# Schematic.net
KiCad netlist of a schematic drawn in EAGLE
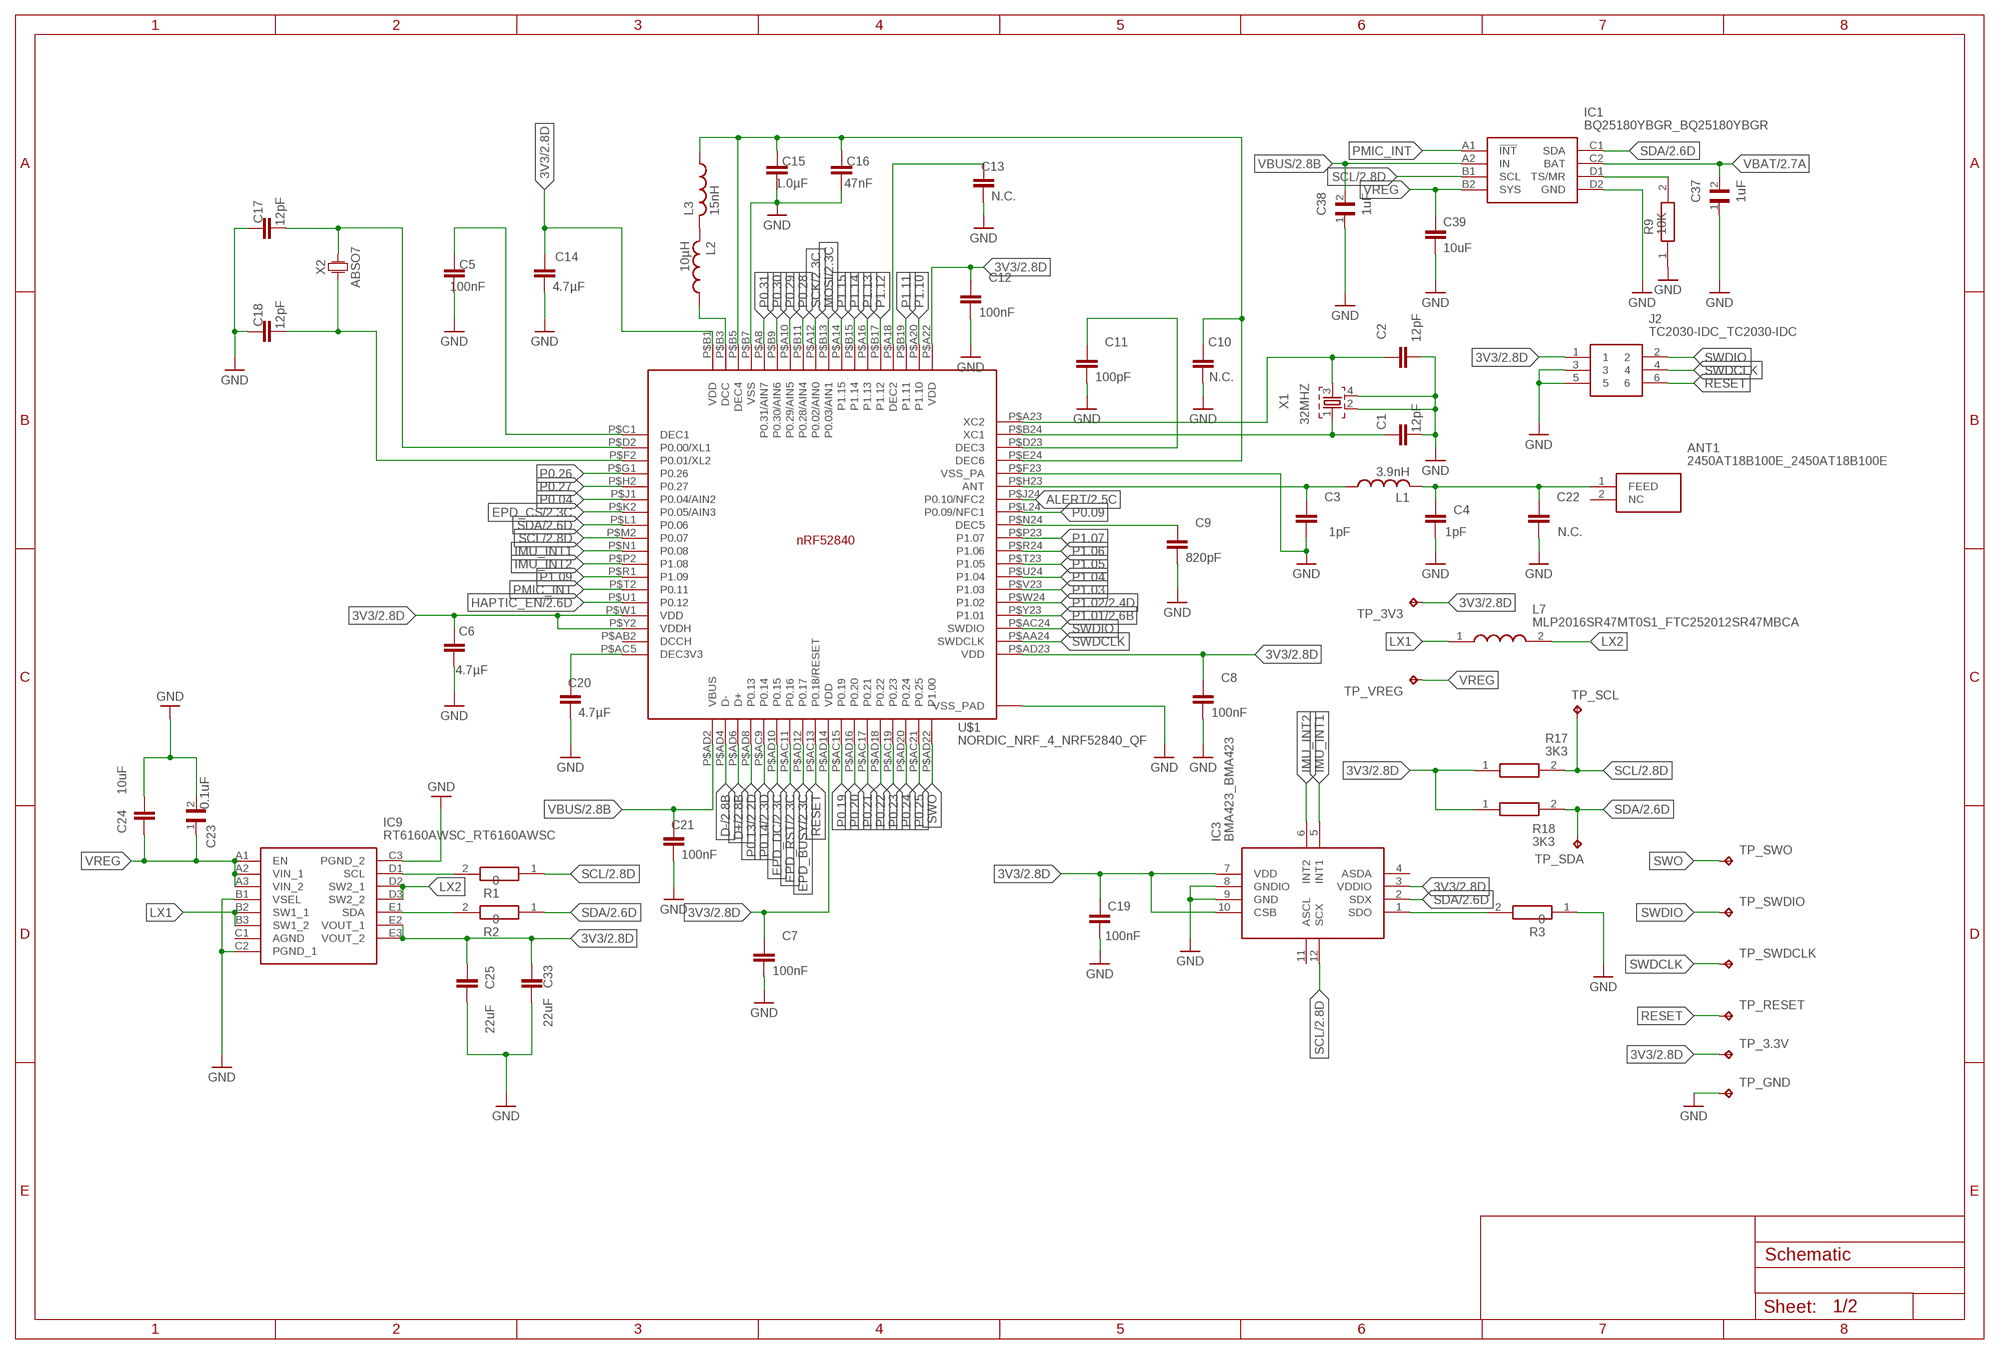
[diagram p0: schematic, sheet 1]
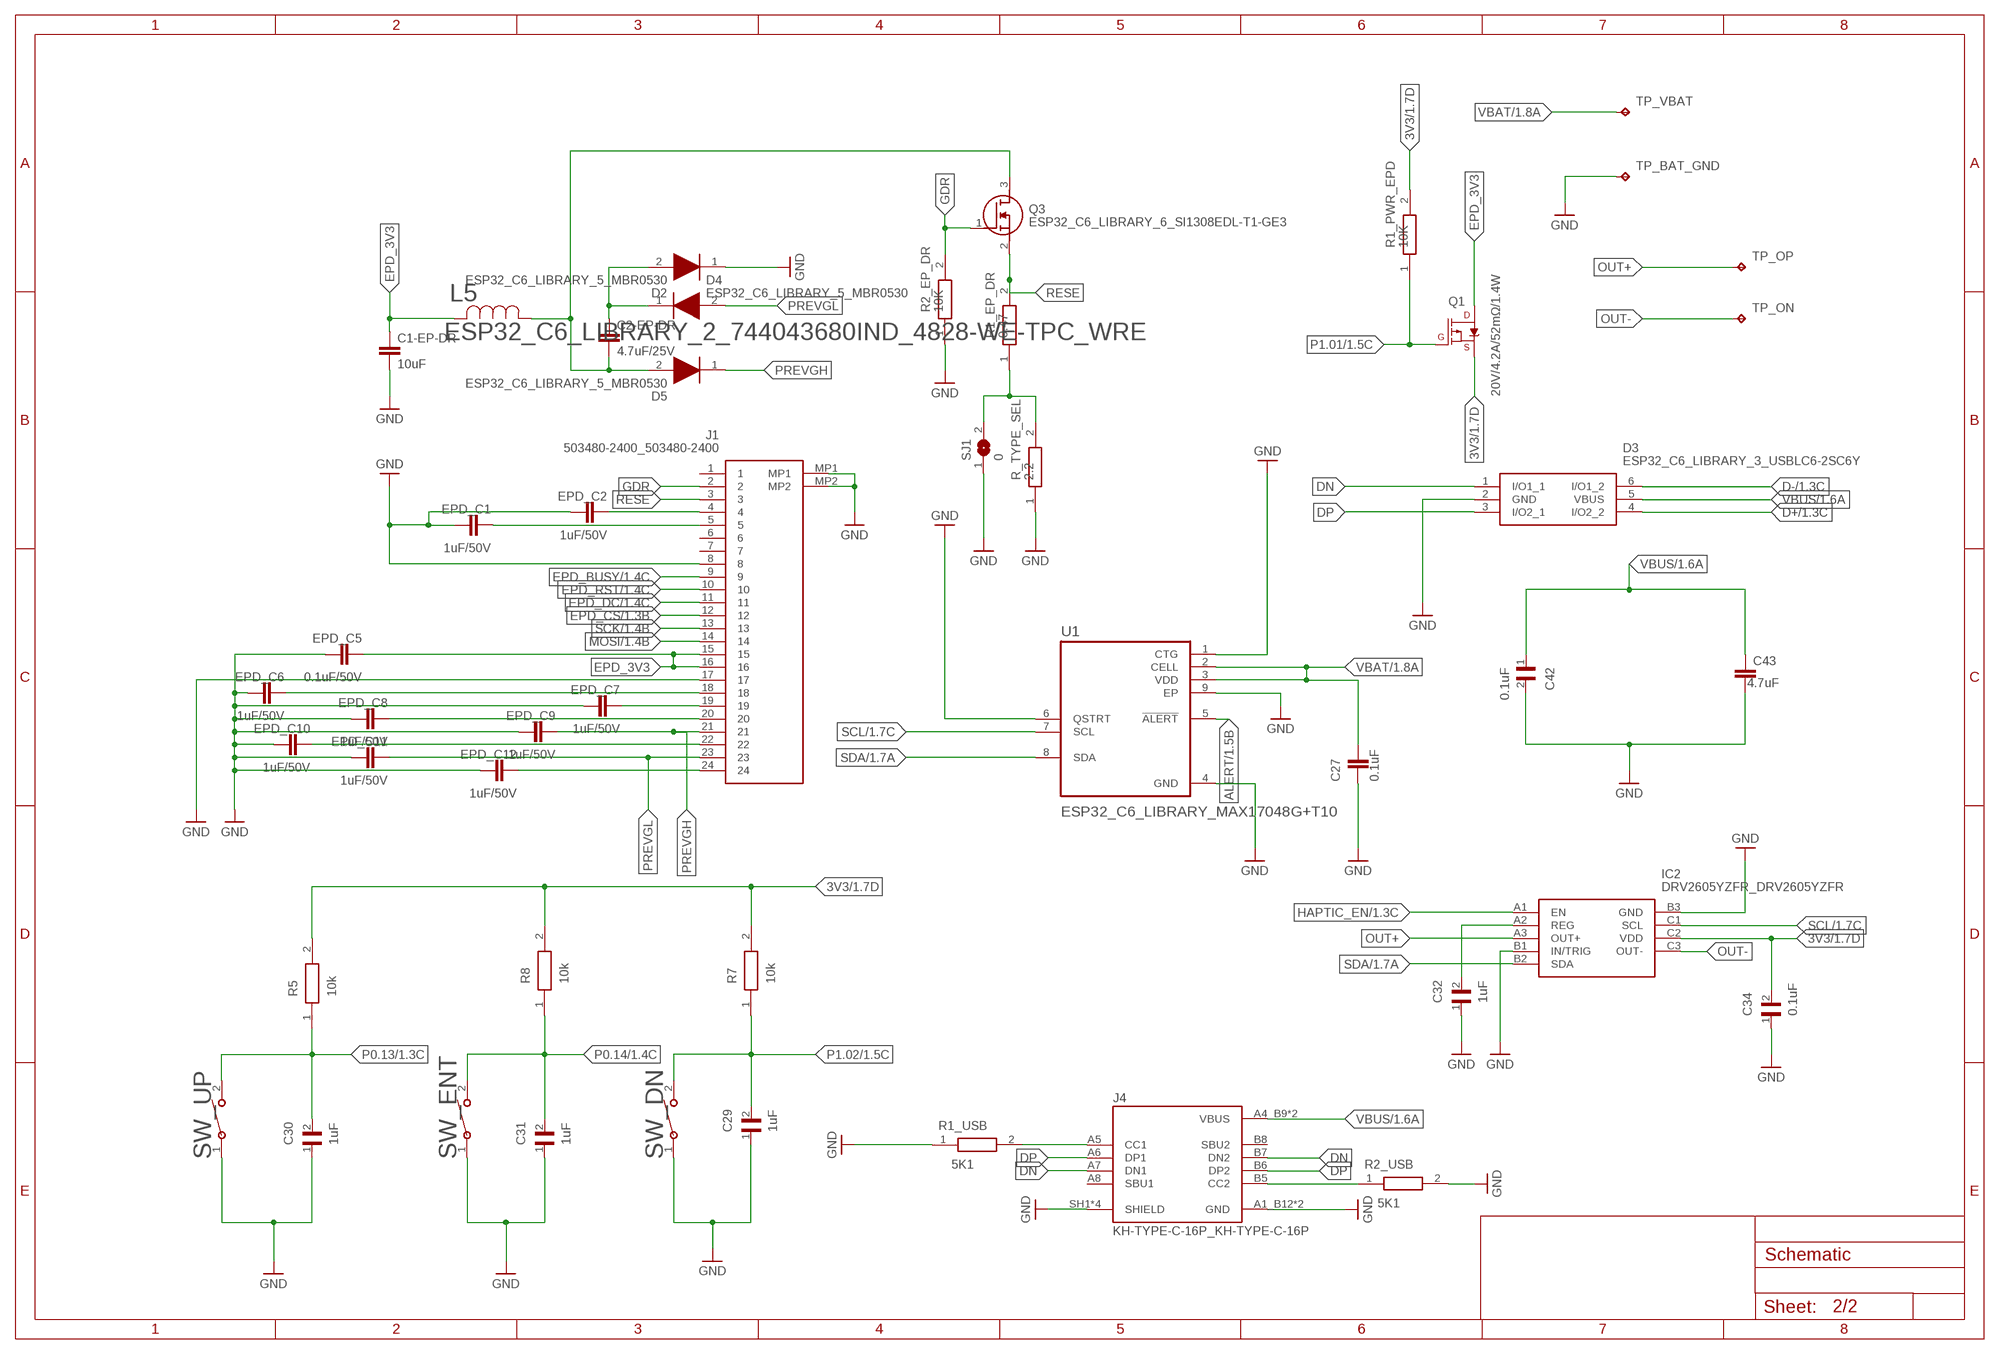
[diagram p1: schematic, sheet 2]

(export (version "E")
  (design (tool "Eeschema 10.0.6"))
  (components
    (comp (ref "C1-EP-DR")
      (value "10uF")
      (footprint "eagle-import:NORDIC_NRF_3_RESC0201_L")
      (libsource (lib "eagle-import") (part "InkTime_v5_vf.HE5F4i0kSp2JyauVwp79Dg_NORDIC_NRF_3_CAPACITOR_0201_L"))
    )
    (comp (ref "C2-EP-DR")
      (value "4.7uF/25V")
      (footprint "eagle-import:NORDIC_NRF_3_RESC0201_L")
      (libsource (lib "eagle-import") (part "InkTime_v5_vf.HE5F4i0kSp2JyauVwp79Dg_NORDIC_NRF_3_CAPACITOR_0201_L"))
    )
    (comp (ref "C27")
      (value "0.1uF")
      (footprint "eagle-import:NORDIC_NRF_3_RESC0201_L")
      (libsource (lib "eagle-import") (part "InkTime_v5_vf.HE5F4i0kSp2JyauVwp79Dg_NORDIC_NRF_3_CAPACITOR_0201_L"))
    )
    (comp (ref "C29")
      (value "1uF")
      (footprint "eagle-import:GRM011R60J152KE01L_1_0201")
      (libsource (lib "eagle-import") (part "GRM011R60J152KE01L_1_GRM011R60J152KE01L"))
    )
    (comp (ref "C30")
      (value "1uF")
      (footprint "eagle-import:GRM011R60J152KE01L_1_0201")
      (libsource (lib "eagle-import") (part "GRM011R60J152KE01L_1_GRM011R60J152KE01L"))
    )
    (comp (ref "C31")
      (value "1uF")
      (footprint "eagle-import:GRM011R60J152KE01L_1_0201")
      (libsource (lib "eagle-import") (part "GRM011R60J152KE01L_1_GRM011R60J152KE01L"))
    )
    (comp (ref "C32")
      (value "1uF")
      (footprint "eagle-import:GRM011R60J152KE01L_1_0201")
      (libsource (lib "eagle-import") (part "GRM011R60J152KE01L_1_GRM011R60J152KE01L"))
    )
    (comp (ref "C34")
      (value "0.1uF")
      (footprint "eagle-import:GRM011R60J152KE01L_1_0201")
      (libsource (lib "eagle-import") (part "GRM011R60J152KE01L_1_GRM011R60J152KE01L"))
    )
    (comp (ref "C42")
      (value "0.1uF")
      (footprint "eagle-import:GRM011R60J152KE01L_1_0201")
      (libsource (lib "eagle-import") (part "GRM011R60J152KE01L_1_GRM011R60J152KE01L"))
    )
    (comp (ref "C43")
      (value "4.7uF")
      (footprint "eagle-import:NORDIC_NRF_3_RESC0201_L")
      (libsource (lib "eagle-import") (part "InkTime_v5_vf.HE5F4i0kSp2JyauVwp79Dg_NORDIC_NRF_3_CAPACITOR_0201_L"))
    )
    (comp (ref "D2")
      (value "ESP32_C6_LIBRARY_5_MBR0530")
      (footprint "eagle-import:ESP32_C6_LIBRARY_5_SOD3716X135N")
      (fields (field (name "MF") "ON Semiconductor") (field (name "MP") "MBR0530"))
      (libsource (lib "eagle-import") (part "ESP32_C6_LIBRARY_5_MBR0530"))
    )
    (comp (ref "D3")
      (value "ESP32_C6_LIBRARY_3_USBLC6-2SC6Y")
      (footprint "eagle-import:ESP32_C6_LIBRARY_3_SOT95P280X145-6N")
      (fields (field (name "MF") "STMicroelectronics") (field (name "MP") "USBLC6-2SC6Y"))
      (libsource (lib "eagle-import") (part "ESP32_C6_LIBRARY_3_USBLC6-2SC6Y"))
    )
    (comp (ref "D4")
      (value "ESP32_C6_LIBRARY_5_MBR0530")
      (footprint "eagle-import:ESP32_C6_LIBRARY_5_SOD3716X135N")
      (fields (field (name "MF") "ON Semiconductor") (field (name "MP") "MBR0530"))
      (libsource (lib "eagle-import") (part "ESP32_C6_LIBRARY_5_MBR0530"))
    )
    (comp (ref "D5")
      (value "ESP32_C6_LIBRARY_5_MBR0530")
      (footprint "eagle-import:ESP32_C6_LIBRARY_5_SOD3716X135N")
      (fields (field (name "MF") "ON Semiconductor") (field (name "MP") "MBR0530"))
      (libsource (lib "eagle-import") (part "ESP32_C6_LIBRARY_5_MBR0530"))
    )
    (comp (ref "EPD_C1")
      (value "1uF/50V")
      (footprint "eagle-import:NORDIC_NRF_3_RESC0201_L")
      (libsource (lib "eagle-import") (part "InkTime_v5_vf.HE5F4i0kSp2JyauVwp79Dg_NORDIC_NRF_3_CAPACITOR_0201_L"))
    )
    (comp (ref "EPD_C2")
      (value "1uF/50V")
      (footprint "eagle-import:NORDIC_NRF_3_RESC0201_L")
      (libsource (lib "eagle-import") (part "InkTime_v5_vf.HE5F4i0kSp2JyauVwp79Dg_NORDIC_NRF_3_CAPACITOR_0201_L"))
    )
    (comp (ref "EPD_C5")
      (value "0.1uF/50V")
      (footprint "eagle-import:NORDIC_NRF_3_RESC0201_L")
      (libsource (lib "eagle-import") (part "InkTime_v5_vf.HE5F4i0kSp2JyauVwp79Dg_NORDIC_NRF_3_CAPACITOR_0201_L"))
    )
    (comp (ref "EPD_C6")
      (value "1uF/50V")
      (footprint "eagle-import:NORDIC_NRF_3_RESC0201_L")
      (libsource (lib "eagle-import") (part "InkTime_v5_vf.HE5F4i0kSp2JyauVwp79Dg_NORDIC_NRF_3_CAPACITOR_0201_L"))
    )
    (comp (ref "EPD_C7")
      (value "1uF/50V")
      (footprint "eagle-import:NORDIC_NRF_3_RESC0201_L")
      (libsource (lib "eagle-import") (part "InkTime_v5_vf.HE5F4i0kSp2JyauVwp79Dg_NORDIC_NRF_3_CAPACITOR_0201_L"))
    )
    (comp (ref "EPD_C8")
      (value "1uF/50V")
      (footprint "eagle-import:NORDIC_NRF_3_RESC0201_L")
      (libsource (lib "eagle-import") (part "InkTime_v5_vf.HE5F4i0kSp2JyauVwp79Dg_NORDIC_NRF_3_CAPACITOR_0201_L"))
    )
    (comp (ref "EPD_C9")
      (value "1uF/50V")
      (footprint "eagle-import:NORDIC_NRF_3_RESC0201_L")
      (libsource (lib "eagle-import") (part "InkTime_v5_vf.HE5F4i0kSp2JyauVwp79Dg_NORDIC_NRF_3_CAPACITOR_0201_L"))
    )
    (comp (ref "EPD_C10")
      (value "1uF/50V")
      (footprint "eagle-import:NORDIC_NRF_3_RESC0201_L")
      (libsource (lib "eagle-import") (part "InkTime_v5_vf.HE5F4i0kSp2JyauVwp79Dg_NORDIC_NRF_3_CAPACITOR_0201_L"))
    )
    (comp (ref "EPD_C11")
      (value "1uF/50V")
      (footprint "eagle-import:NORDIC_NRF_3_RESC0201_L")
      (libsource (lib "eagle-import") (part "InkTime_v5_vf.HE5F4i0kSp2JyauVwp79Dg_NORDIC_NRF_3_CAPACITOR_0201_L"))
    )
    (comp (ref "EPD_C12")
      (value "1uF/50V")
      (footprint "eagle-import:NORDIC_NRF_3_RESC0201_L")
      (libsource (lib "eagle-import") (part "InkTime_v5_vf.HE5F4i0kSp2JyauVwp79Dg_NORDIC_NRF_3_CAPACITOR_0201_L"))
    )
    (comp (ref "IC2")
      (value "DRV2605YZFR_DRV2605YZFR")
      (footprint "eagle-import:DRV2605YZFR_BGA9C50P3X3_144X144X62")
      (fields (field (name "MANUFACTURER_PART_NUMBER") "DRV2605YZFR"))
      (libsource (lib "eagle-import") (part "DRV2605YZFR_DRV2605YZFR"))
    )
    (comp (ref "J1")
      (value "503480-2400_503480-2400")
      (footprint "eagle-import:503480-2400_5034802400")
      (fields
        (field (name "MANUFACTURER_PART_NUMBER") "503480-2400")
        (field (name "MOUSER_PART_NUMBER") "538-503480-2400")
      )
      (libsource (lib "eagle-import") (part "503480-2400_503480-2400"))
    )
    (comp (ref "J4")
      (value "KH-TYPE-C-16P_KH-TYPE-C-16P")
      (footprint "eagle-import:KH-TYPE-C-16P_KINGHELM_KH-TYPE-C-16P")
      (fields (field (name "MF") "kinghelm") (field (name "MP") "KH-TYPE-C-16P"))
      (libsource (lib "eagle-import") (part "KH-TYPE-C-16P_KH-TYPE-C-16P"))
    )
    (comp (ref "L5")
      (value "ESP32_C6_LIBRARY_2_744043680IND_4828-WE-TPC_WRE")
      (footprint "eagle-import:ESP32_C6_LIBRARY_2_IND_4828-WE-TPC_WRE")
      (fields
        (field (name "MANUFACTURER_PART_NUMBER") "744043680")
        (field (name "COPYRIGHT") "Copyright (C) 2024 Ultra Librarian. All rights reserved.")
      )
      (libsource (lib "eagle-import") (part "ESP32_C6_LIBRARY_2_744043680IND_4828-WE-TPC_WRE"))
    )
    (comp (ref "Q1")
      (value "20V/4.2A/52mΩ/1.4W")
      (footprint "eagle-import:ESP32_C6_LIBRARY_4_ESP32_C6_LIBRARY_4_ESP32_C6_LIBRARY_4_ESP32_C6_LIBRARY_4_ESP32_WROVER_SPARKFUN-DISCRETESEMI_SOT23-3")
      (libsource (lib "eagle-import") (part "ESP32_C6_LIBRARY_4_ESP32_WROVER_SPARKFUN-DISCRETESEMI_MOSFET_PCH-DMG2305UX-7"))
    )
    (comp (ref "Q3")
      (value "ESP32_C6_LIBRARY_6_SI1308EDL-T1-GE3")
      (footprint "eagle-import:ESP32_C6_LIBRARY_6_SOT65P210X110-3N")
      (fields (field (name "MF") "Vishay Siliconix") (field (name "MP") "SI1308EDL-T1-GE3"))
      (libsource (lib "eagle-import") (part "ESP32_C6_LIBRARY_6_SI1308EDL-T1-GE3"))
    )
    (comp (ref "R1_EP_DR")
      (value "0.47")
      (footprint "eagle-import:CPF0201D7K68C1_0201")
      (libsource (lib "eagle-import") (part "InkTime_v5_vf.HE5F4i0kSp2JyauVwp79Dg_CPF0201D7K68C1_CPF0201D7K68C1"))
    )
    (comp (ref "R1_PWR_EPD")
      (value "10K")
      (footprint "eagle-import:CPF0201D7K68C1_0201")
      (libsource (lib "eagle-import") (part "InkTime_v5_vf.HE5F4i0kSp2JyauVwp79Dg_CPF0201D7K68C1_CPF0201D7K68C1"))
    )
    (comp (ref "R1_USB")
      (value "5K1")
      (footprint "eagle-import:CPF0201D7K68C1_0201")
      (libsource (lib "eagle-import") (part "CPF0201D7K68C1_CPF0201D7K68C1"))
    )
    (comp (ref "R2_EP_DR")
      (value "10K")
      (footprint "eagle-import:CPF0201D7K68C1_0201")
      (libsource (lib "eagle-import") (part "InkTime_v5_vf.HE5F4i0kSp2JyauVwp79Dg_CPF0201D7K68C1_CPF0201D7K68C1"))
    )
    (comp (ref "R2_USB")
      (value "5K1")
      (footprint "eagle-import:CPF0201D7K68C1_0201")
      (libsource (lib "eagle-import") (part "CPF0201D7K68C1_CPF0201D7K68C1"))
    )
    (comp (ref "R5")
      (value "10k")
      (footprint "eagle-import:CPF0201D7K68C1_0201")
      (libsource (lib "eagle-import") (part "CPF0201D7K68C1_CPF0201D7K68C1"))
    )
    (comp (ref "R7")
      (value "10k")
      (footprint "eagle-import:CPF0201D7K68C1_0201")
      (libsource (lib "eagle-import") (part "CPF0201D7K68C1_CPF0201D7K68C1"))
    )
    (comp (ref "R8")
      (value "10k")
      (footprint "eagle-import:CPF0201D7K68C1_0201")
      (libsource (lib "eagle-import") (part "CPF0201D7K68C1_CPF0201D7K68C1"))
    )
    (comp (ref "R_TYPE_SEL")
      (value "2.2")
      (footprint "eagle-import:CPF0201D7K68C1_0201")
      (libsource (lib "eagle-import") (part "InkTime_v5_vf.HE5F4i0kSp2JyauVwp79Dg_CPF0201D7K68C1_CPF0201D7K68C1"))
    )
    (comp (ref "SJ1")
      (value "0")
      (footprint "eagle-import:ESP32_C6_LIBRARY_7_JUMPER_SJ")
      (libsource (lib "eagle-import") (part "ESP32_C6_LIBRARY_7_JUMPER_SJ"))
    )
    (comp (ref "SW_DN")
      (value "2025-10-22_07-23-44_LIBRARY_EVP-AKE31ASW_EVP-AKE31A_PAN")
      (footprint "eagle-import:2025-10-22_07-23-44_LIBRARY_SW_EVP-AKE31A_PAN")
      (fields
        (field (name "MANUFACTURER_PART_NUMBER") "EVP-AKE31A")
        (field (name "COPYRIGHT") "Copyright (C) 2025 Ultra Librarian. All rights reserved.")
      )
      (libsource (lib "eagle-import") (part "2025-10-22_07-23-44_LIBRARY_EVP-AKE31ASW_EVP-AKE31A_PAN"))
    )
    (comp (ref "SW_ENT")
      (value "2025-10-22_07-23-44_LIBRARY_EVP-AKE31ASW_EVP-AKE31A_PAN")
      (footprint "eagle-import:2025-10-22_07-23-44_LIBRARY_SW_EVP-AKE31A_PAN")
      (fields
        (field (name "MANUFACTURER_PART_NUMBER") "EVP-AKE31A")
        (field (name "COPYRIGHT") "Copyright (C) 2025 Ultra Librarian. All rights reserved.")
      )
      (libsource (lib "eagle-import") (part "2025-10-22_07-23-44_LIBRARY_EVP-AKE31ASW_EVP-AKE31A_PAN"))
    )
    (comp (ref "SW_UP")
      (value "2025-10-22_07-23-44_LIBRARY_EVP-AKE31ASW_EVP-AKE31A_PAN")
      (footprint "eagle-import:2025-10-22_07-23-44_LIBRARY_SW_EVP-AKE31A_PAN")
      (fields
        (field (name "MANUFACTURER_PART_NUMBER") "EVP-AKE31A")
        (field (name "COPYRIGHT") "Copyright (C) 2025 Ultra Librarian. All rights reserved.")
      )
      (libsource (lib "eagle-import") (part "2025-10-22_07-23-44_LIBRARY_EVP-AKE31ASW_EVP-AKE31A_PAN"))
    )
    (comp (ref "TP_BAT_GND")
      (value "HECTOR_WATCH_1_TPTP20R")
      (footprint "eagle-import:HECTOR_WATCH_1_TP20R")
      (libsource (lib "eagle-import") (part "HECTOR_WATCH_1_TPTP20R"))
    )
    (comp (ref "TP_ON")
      (value "HECTOR_WATCH_1_TPTP20R")
      (footprint "eagle-import:HECTOR_WATCH_1_TP20R")
      (libsource (lib "eagle-import") (part "HECTOR_WATCH_1_TPTP20R"))
    )
    (comp (ref "TP_OP")
      (value "HECTOR_WATCH_1_TPTP20R")
      (footprint "eagle-import:HECTOR_WATCH_1_TP20R")
      (libsource (lib "eagle-import") (part "HECTOR_WATCH_1_TPTP20R"))
    )
    (comp (ref "TP_VBAT")
      (value "HECTOR_WATCH_1_TPTP20R")
      (footprint "eagle-import:HECTOR_WATCH_1_TP20R")
      (libsource (lib "eagle-import") (part "HECTOR_WATCH_1_TPTP20R"))
    )
    (comp (ref "U1")
      (value "ESP32_C6_LIBRARY_MAX17048G+T10")
      (footprint "eagle-import:ESP32_C6_LIBRARY_SON50P200X200X80-9N")
      (fields (field (name "MF") "Analog Devices") (field (name "MP") "MAX17048G+T10"))
      (libsource (lib "eagle-import") (part "ESP32_C6_LIBRARY_MAX17048G+T10"))
    )
    (comp (ref "ANT1")
      (value "2450AT18B100E_2450AT18B100E")
      (footprint "eagle-import:2450AT18B100E_ANTC3216X140N")
      (fields
        (field (name "ARROW_PART_NUMBER") "2450AT18B100E")
        (field (name "MOUSER_PART_NUMBER") "609-2450AT18B100E")
      )
      (libsource (lib "eagle-import") (part "2450AT18B100E_2450AT18B100E"))
    )
    (comp (ref "C1")
      (value "12pF")
      (footprint "eagle-import:NORDIC_NRF_3_RESC0201_L")
      (libsource (lib "eagle-import") (part "NORDIC_NRF_3_CAPACITOR_0201_L"))
    )
    (comp (ref "C2")
      (value "12pF")
      (footprint "eagle-import:NORDIC_NRF_3_RESC0201_L")
      (libsource (lib "eagle-import") (part "NORDIC_NRF_3_CAPACITOR_0201_L"))
    )
    (comp (ref "C3")
      (value "1pF")
      (footprint "eagle-import:NORDIC_NRF_3_RESC0201_L")
      (libsource (lib "eagle-import") (part "NORDIC_NRF_3_CAPACITOR_0201_L"))
    )
    (comp (ref "C4")
      (value "1pF")
      (footprint "eagle-import:NORDIC_NRF_3_RESC0201_L")
      (libsource (lib "eagle-import") (part "NORDIC_NRF_3_CAPACITOR_0201_L"))
    )
    (comp (ref "C5")
      (value "100nF")
      (footprint "eagle-import:NORDIC_NRF_3_RESC0201_L")
      (libsource (lib "eagle-import") (part "NORDIC_NRF_3_CAPACITOR_0201_L"))
    )
    (comp (ref "C6")
      (value "4.7µF")
      (footprint "eagle-import:NORDIC_NRF_3_RESC0201_L")
      (libsource (lib "eagle-import") (part "NORDIC_NRF_3_CAPACITOR_0201_L"))
    )
    (comp (ref "C7")
      (value "100nF")
      (footprint "eagle-import:NORDIC_NRF_3_RESC0201_L")
      (libsource (lib "eagle-import") (part "NORDIC_NRF_3_CAPACITOR_0201_L"))
    )
    (comp (ref "C8")
      (value "100nF")
      (footprint "eagle-import:NORDIC_NRF_3_RESC0201_L")
      (libsource (lib "eagle-import") (part "NORDIC_NRF_3_CAPACITOR_0201_L"))
    )
    (comp (ref "C9")
      (value "820pF")
      (footprint "eagle-import:NORDIC_NRF_3_RESC0201_L")
      (libsource (lib "eagle-import") (part "NORDIC_NRF_3_CAPACITOR_0201_L"))
    )
    (comp (ref "C10")
      (value "N.C.")
      (footprint "eagle-import:NORDIC_NRF_3_RESC0201_L")
      (libsource (lib "eagle-import") (part "NORDIC_NRF_3_CAPACITOR_0201_L"))
    )
    (comp (ref "C11")
      (value "100pF")
      (footprint "eagle-import:NORDIC_NRF_3_RESC0201_L")
      (libsource (lib "eagle-import") (part "NORDIC_NRF_3_CAPACITOR_0201_L"))
    )
    (comp (ref "C12")
      (value "100nF")
      (footprint "eagle-import:NORDIC_NRF_3_RESC0201_L")
      (libsource (lib "eagle-import") (part "NORDIC_NRF_3_CAPACITOR_0201_L"))
    )
    (comp (ref "C13")
      (value "N.C.")
      (footprint "eagle-import:NORDIC_NRF_3_RESC0201_L")
      (libsource (lib "eagle-import") (part "NORDIC_NRF_3_CAPACITOR_0201_L"))
    )
    (comp (ref "C14")
      (value "4.7µF")
      (footprint "eagle-import:NORDIC_NRF_3_RESC0201_L")
      (libsource (lib "eagle-import") (part "NORDIC_NRF_3_CAPACITOR_0201_L"))
    )
    (comp (ref "C15")
      (value "1.0µF")
      (footprint "eagle-import:NORDIC_NRF_3_RESC0201_L")
      (libsource (lib "eagle-import") (part "NORDIC_NRF_3_CAPACITOR_0201_L"))
    )
    (comp (ref "C16")
      (value "47nF")
      (footprint "eagle-import:NORDIC_NRF_3_RESC0201_L")
      (libsource (lib "eagle-import") (part "NORDIC_NRF_3_CAPACITOR_0201_L"))
    )
    (comp (ref "C17")
      (value "12pF")
      (footprint "eagle-import:NORDIC_NRF_3_RESC0201_L")
      (libsource (lib "eagle-import") (part "NORDIC_NRF_3_CAPACITOR_0201_L"))
    )
    (comp (ref "C18")
      (value "12pF")
      (footprint "eagle-import:NORDIC_NRF_3_RESC0201_L")
      (libsource (lib "eagle-import") (part "NORDIC_NRF_3_CAPACITOR_0201_L"))
    )
    (comp (ref "C19")
      (value "100nF")
      (footprint "eagle-import:NORDIC_NRF_3_RESC0201_L")
      (libsource (lib "eagle-import") (part "NORDIC_NRF_3_CAPACITOR_0201_L"))
    )
    (comp (ref "C20")
      (value "4.7µF")
      (footprint "eagle-import:NORDIC_NRF_3_RESC0201_L")
      (libsource (lib "eagle-import") (part "NORDIC_NRF_3_CAPACITOR_0201_L"))
    )
    (comp (ref "C21")
      (value "100nF")
      (footprint "eagle-import:NORDIC_NRF_3_RESC0201_L")
      (libsource (lib "eagle-import") (part "NORDIC_NRF_3_CAPACITOR_0201_L"))
    )
    (comp (ref "C22")
      (value "N.C.")
      (footprint "eagle-import:NORDIC_NRF_3_RESC0201_L")
      (libsource (lib "eagle-import") (part "NORDIC_NRF_3_CAPACITOR_0201_L"))
    )
    (comp (ref "C23")
      (value "0.1uF")
      (footprint "eagle-import:GRM011R60J152KE01L_2_CAPC0201X13N")
      (fields (field (name "MF") "Murata") (field (name "MP") "GRM011R60J152KE01L"))
      (libsource (lib "eagle-import") (part "GRM011R60J152KE01L_2_GRM011R60J152KE01L"))
    )
    (comp (ref "C24")
      (value "10uF")
      (footprint "eagle-import:NORDIC_NRF_3_RESC0201_L")
      (libsource (lib "eagle-import") (part "NORDIC_NRF_3_CAPACITOR_0201_L"))
    )
    (comp (ref "C25")
      (value "22uF")
      (footprint "eagle-import:NORDIC_NRF_3_RESC0201_L")
      (libsource (lib "eagle-import") (part "NORDIC_NRF_3_CAPACITOR_0201_L"))
    )
    (comp (ref "C33")
      (value "22uF")
      (footprint "eagle-import:NORDIC_NRF_3_RESC0201_L")
      (libsource (lib "eagle-import") (part "NORDIC_NRF_3_CAPACITOR_0201_L"))
    )
    (comp (ref "C37")
      (value "1uF")
      (footprint "eagle-import:GRM011R60J152KE01L_2_CAPC0201X13N")
      (fields (field (name "MF") "Murata") (field (name "MP") "GRM011R60J152KE01L"))
      (libsource (lib "eagle-import") (part "GRM011R60J152KE01L_2_GRM011R60J152KE01L"))
    )
    (comp (ref "C38")
      (value "1uF")
      (footprint "eagle-import:GRM011R60J152KE01L_2_CAPC0201X13N")
      (fields (field (name "MF") "Murata") (field (name "MP") "GRM011R60J152KE01L"))
      (libsource (lib "eagle-import") (part "GRM011R60J152KE01L_2_GRM011R60J152KE01L"))
    )
    (comp (ref "C39")
      (value "10uF")
      (footprint "eagle-import:NORDIC_NRF_3_RESC0201_L")
      (libsource (lib "eagle-import") (part "NORDIC_NRF_3_CAPACITOR_0201_L"))
    )
    (comp (ref "IC1")
      (value "BQ25180YBGR_BQ25180YBGR")
      (footprint "eagle-import:BQ25180YBGR_BGA8C40P2X4_100X155X50")
      (fields
        (field (name "MANUFACTURER_PART_NUMBER") "BQ25180YBGR")
        (field (name "MOUSER_PART_NUMBER") "595-BQ25180YBGR")
      )
      (libsource (lib "eagle-import") (part "BQ25180YBGR_BQ25180YBGR"))
    )
    (comp (ref "IC3")
      (value "BMA423_BMA423")
      (footprint "eagle-import:BMA423_BMA423")
      (fields (field (name "ARROW_PART_NUMBER") "BMA423") (field (name "MOUSER_PART_NUMBER") "262-BMA423"))
      (libsource (lib "eagle-import") (part "BMA423_BMA423"))
    )
    (comp (ref "IC9")
      (value "RT6160AWSC_RT6160AWSC")
      (footprint "eagle-import:RT6160AWSC_BGA15C40P3X5_140X230X60")
      (fields
        (field (name "MANUFACTURER_PART_NUMBER") "RT6160AWSC")
        (field (name "MOUSER_PART_NUMBER") "835-RT6160AWSC")
      )
      (libsource (lib "eagle-import") (part "RT6160AWSC_RT6160AWSC"))
    )
    (comp (ref "J2")
      (value "TC2030-IDC_TC2030-IDC")
      (footprint "eagle-import:TC2030-IDC_TC2030IDC")
      (fields (field (name "MANUFACTURER_PART_NUMBER") "TC2030-IDC"))
      (libsource (lib "eagle-import") (part "TC2030-IDC_TC2030-IDC"))
    )
    (comp (ref "L1")
      (value "3.9nH")
      (footprint "eagle-import:NORDIC_NRF_2_RESC0402_L")
      (libsource (lib "eagle-import") (part "NORDIC_NRF_2_INDUCTOR_0402_L"))
    )
    (comp (ref "L2")
      (value "10µH")
      (footprint "eagle-import:NORDIC_NRF_2_RESC0402_L")
      (libsource (lib "eagle-import") (part "NORDIC_NRF_2_INDUCTOR_0402_L"))
    )
    (comp (ref "L3")
      (value "15nH")
      (footprint "eagle-import:NORDIC_NRF_2_RESC0402_L")
      (libsource (lib "eagle-import") (part "NORDIC_NRF_2_INDUCTOR_0402_L"))
    )
    (comp (ref "L7")
      (value "MLP2016SR47MT0S1_FTC252012SR47MBCA")
      (footprint "eagle-import:MLP2016SR47MT0S1_INDC2016X100N")
      (fields (field (name "MANUFACTURER_PART_NUMBER") "FTC252012SR47MBCA"))
      (libsource (lib "eagle-import") (part "MLP2016SR47MT0S1_FTC252012SR47MBCA"))
    )
    (comp (ref "R1")
      (value "0")
      (footprint "eagle-import:ERA-1AEB3401C_0201")
      (libsource (lib "eagle-import") (part "ERA-1AEB3401C_CPF0201D7K68C1"))
    )
    (comp (ref "R2")
      (value "0")
      (footprint "eagle-import:ERA-1AEB3401C_0201")
      (libsource (lib "eagle-import") (part "ERA-1AEB3401C_CPF0201D7K68C1"))
    )
    (comp (ref "R3")
      (value "0")
      (footprint "eagle-import:ERA-1AEB3401C_0201")
      (libsource (lib "eagle-import") (part "ERA-1AEB3401C_CPF0201D7K68C1"))
    )
    (comp (ref "R9")
      (value "10K")
      (footprint "eagle-import:ERA-1AEB3401C_0201")
      (libsource (lib "eagle-import") (part "ERA-1AEB3401C_CPF0201D7K68C1"))
    )
    (comp (ref "R17")
      (value "3K3")
      (footprint "eagle-import:ERA-1AEB3401C_0201")
      (libsource (lib "eagle-import") (part "ERA-1AEB3401C_CPF0201D7K68C1"))
    )
    (comp (ref "R18")
      (value "3K3")
      (footprint "eagle-import:ERA-1AEB3401C_0201")
      (libsource (lib "eagle-import") (part "ERA-1AEB3401C_CPF0201D7K68C1"))
    )
    (comp (ref "TP_3.3V")
      (value "HECTOR_WATCH_1_TPTP20R")
      (footprint "eagle-import:HECTOR_WATCH_1_TP20R")
      (libsource (lib "eagle-import") (part "InkTime_v5_vf.HE5F4i0kSp2JyauVwp79Dg_HECTOR_WATCH_1_TPTP20R"))
    )
    (comp (ref "TP_3V3")
      (value "HECTOR_WATCH_1_TPTP20R")
      (footprint "eagle-import:HECTOR_WATCH_1_TP20R")
      (libsource (lib "eagle-import") (part "InkTime_v5_vf.HE5F4i0kSp2JyauVwp79Dg_HECTOR_WATCH_1_TPTP20R"))
    )
    (comp (ref "TP_GND")
      (value "HECTOR_WATCH_1_TPTP20R")
      (footprint "eagle-import:HECTOR_WATCH_1_TP20R")
      (libsource (lib "eagle-import") (part "InkTime_v5_vf.HE5F4i0kSp2JyauVwp79Dg_HECTOR_WATCH_1_TPTP20R"))
    )
    (comp (ref "TP_RESET")
      (value "HECTOR_WATCH_1_TPTP20R")
      (footprint "eagle-import:HECTOR_WATCH_1_TP20R")
      (libsource (lib "eagle-import") (part "InkTime_v5_vf.HE5F4i0kSp2JyauVwp79Dg_HECTOR_WATCH_1_TPTP20R"))
    )
    (comp (ref "TP_SCL")
      (value "HECTOR_WATCH_1_TPTP20R")
      (footprint "eagle-import:HECTOR_WATCH_1_TP20R")
      (libsource (lib "eagle-import") (part "InkTime_v5_vf.HE5F4i0kSp2JyauVwp79Dg_HECTOR_WATCH_1_TPTP20R"))
    )
    (comp (ref "TP_SDA")
      (value "HECTOR_WATCH_1_TPTP20R")
      (footprint "eagle-import:HECTOR_WATCH_1_TP20R")
      (libsource (lib "eagle-import") (part "InkTime_v5_vf.HE5F4i0kSp2JyauVwp79Dg_HECTOR_WATCH_1_TPTP20R"))
    )
    (comp (ref "TP_SWDCLK")
      (value "HECTOR_WATCH_1_TPTP20R")
      (footprint "eagle-import:HECTOR_WATCH_1_TP20R")
      (libsource (lib "eagle-import") (part "InkTime_v5_vf.HE5F4i0kSp2JyauVwp79Dg_HECTOR_WATCH_1_TPTP20R"))
    )
    (comp (ref "TP_SWDIO")
      (value "HECTOR_WATCH_1_TPTP20R")
      (footprint "eagle-import:HECTOR_WATCH_1_TP20R")
      (libsource (lib "eagle-import") (part "InkTime_v5_vf.HE5F4i0kSp2JyauVwp79Dg_HECTOR_WATCH_1_TPTP20R"))
    )
    (comp (ref "TP_SWO")
      (value "HECTOR_WATCH_1_TPTP20R")
      (footprint "eagle-import:HECTOR_WATCH_1_TP20R")
      (libsource (lib "eagle-import") (part "InkTime_v5_vf.HE5F4i0kSp2JyauVwp79Dg_HECTOR_WATCH_1_TPTP20R"))
    )
    (comp (ref "TP_VREG")
      (value "HECTOR_WATCH_1_TPTP20R")
      (footprint "eagle-import:HECTOR_WATCH_1_TP20R")
      (libsource (lib "eagle-import") (part "InkTime_v5_vf.HE5F4i0kSp2JyauVwp79Dg_HECTOR_WATCH_1_TPTP20R"))
    )
    (comp (ref "U$1")
      (value "NORDIC_NRF_4_NRF52840_QF")
      (footprint "eagle-import:NORDIC_NRF_4_AQFN50P700X700X85_HS-74N")
      (libsource (lib "eagle-import") (part "NORDIC_NRF_4_NRF52840_QF"))
    )
    (comp (ref "X1")
      (value "32MHZ")
      (footprint "eagle-import:NORDIC_NRF_BT-XTAL_2016_N")
      (libsource (lib "eagle-import") (part "NORDIC_NRF_XTAL_32MHZ"))
    )
    (comp (ref "X2")
      (value "ABSO7")
      (footprint "eagle-import:XTAL_ABS07-32.768KHZ-T")
      (fields
        (field (name "MANUFACTURER") "Abracon LLC")
        (field (name "MPN") "ABS07-32.768KHZ-T")
        (field (name "TOLERANCE") "±20 ppm")
      )
      (libsource (lib "eagle-import") (part "ABSO7"))
    )
  )
  (nets
    (net (code "1") (name "3V3") (class "Default")
      (node (ref "C12") (pin "2") (pinfunction "2_2") (pintype "passive"))
      (node (ref "C14") (pin "1") (pinfunction "1_1") (pintype "passive"))
      (node (ref "C19") (pin "2") (pinfunction "2_2") (pintype "passive"))
      (node (ref "C25") (pin "2") (pinfunction "2_2") (pintype "passive"))
      (node (ref "C33") (pin "1") (pinfunction "1_1") (pintype "passive"))
      (node (ref "C34") (pin "2") (pinfunction "2_2") (pintype "passive"))
      (node (ref "C6") (pin "1") (pinfunction "1_1") (pintype "passive"))
      (node (ref "C7") (pin "2") (pinfunction "2_2") (pintype "passive"))
      (node (ref "C8") (pin "2") (pinfunction "2_2") (pintype "passive"))
      (node (ref "IC2") (pin "C2") (pinfunction "VDD_C2") (pintype "bidirectional"))
      (node (ref "IC3") (pin "10") (pinfunction "CSB_10") (pintype "bidirectional"))
      (node (ref "IC3") (pin "3") (pinfunction "VDDIO_3") (pintype "bidirectional"))
      (node (ref "IC3") (pin "7") (pinfunction "VDD_7") (pintype "bidirectional"))
      (node (ref "IC9") (pin "E2") (pinfunction "VOUT_1_E2") (pintype "bidirectional"))
      (node (ref "IC9") (pin "E3") (pinfunction "VOUT_2_E3") (pintype "bidirectional"))
      (node (ref "J2") (pin "1") (pinfunction "1_1") (pintype "bidirectional"))
      (node (ref "Q1") (pin "2") (pinfunction "S_2") (pintype "bidirectional"))
      (node (ref "R17") (pin "1") (pinfunction "1_1") (pintype "bidirectional"))
      (node (ref "R18") (pin "1") (pinfunction "1_1") (pintype "bidirectional"))
      (node (ref "R1_PWR_EPD") (pin "2") (pinfunction "2_2") (pintype "bidirectional"))
      (node (ref "R5") (pin "2") (pinfunction "2_2") (pintype "bidirectional"))
      (node (ref "R7") (pin "2") (pinfunction "2_2") (pintype "bidirectional"))
      (node (ref "R8") (pin "2") (pinfunction "2_2") (pintype "bidirectional"))
      (node (ref "TP_3.3V") (pin "TP") (pinfunction "TP_TP") (pintype "input"))
      (node (ref "TP_3V3") (pin "TP") (pinfunction "TP_TP") (pintype "input"))
      (node (ref "U$1") (pin "P$A22") (pinfunction "VDD_P$A22") (pintype "power_in"))
      (node (ref "U$1") (pin "P$AD14") (pinfunction "VDD_P$AD14") (pintype "power_in"))
      (node (ref "U$1") (pin "P$AD23") (pinfunction "VDD_P$AD23") (pintype "power_in"))
      (node (ref "U$1") (pin "P$B1") (pinfunction "VDD_P$B1") (pintype "power_in"))
      (node (ref "U$1") (pin "P$W1") (pinfunction "VDD_P$W1") (pintype "power_in"))
      (node (ref "U$1") (pin "P$Y2") (pinfunction "VDDH_P$Y2") (pintype "power_in"))
    )
    (net (code "2") (name "ALERT") (class "Default")
      (node (ref "U$1") (pin "P$J24") (pinfunction "P0.10/NFC2_P$J24") (pintype "bidirectional"))
      (node (ref "U1") (pin "5") (pinfunction "~{ALERT}_5") (pintype "output"))
    )
    (net (code "3") (name "D+") (class "Default")
      (node (ref "D3") (pin "4") (pinfunction "I/O2_2_4") (pintype "bidirectional"))
      (node (ref "U$1") (pin "P$AD6") (pinfunction "D+_P$AD6") (pintype "bidirectional"))
    )
    (net (code "4") (name "D-") (class "Default")
      (node (ref "D3") (pin "6") (pinfunction "I/O1_2_6") (pintype "bidirectional"))
      (node (ref "U$1") (pin "P$AD4") (pinfunction "D-_P$AD4") (pintype "bidirectional"))
    )
    (net (code "5") (name "DN") (class "Default")
      (node (ref "D3") (pin "1") (pinfunction "I/O1_1_1") (pintype "bidirectional"))
      (node (ref "J4") (pin "A7") (pinfunction "DN1_A7") (pintype "bidirectional"))
      (node (ref "J4") (pin "B7") (pinfunction "DN2_B7") (pintype "bidirectional"))
    )
    (net (code "6") (name "DP") (class "Default")
      (node (ref "D3") (pin "3") (pinfunction "I/O2_1_3") (pintype "bidirectional"))
      (node (ref "J4") (pin "A6") (pinfunction "DP1_A6") (pintype "bidirectional"))
      (node (ref "J4") (pin "B6") (pinfunction "DP2_B6") (pintype "bidirectional"))
    )
    (net (code "7") (name "EPD_3V3") (class "Default")
      (node (ref "C1-EP-DR") (pin "1") (pinfunction "1_1") (pintype "passive"))
      (node (ref "EPD_C5") (pin "2") (pinfunction "2_2") (pintype "passive"))
      (node (ref "J1") (pin "15") (pinfunction "15_15") (pintype "bidirectional"))
      (node (ref "J1") (pin "16") (pinfunction "16_16") (pintype "bidirectional"))
      (node (ref "L5") (pin "2") (pinfunction "2_2") (pintype "passive"))
      (node (ref "Q1") (pin "3") (pinfunction "D_3") (pintype "bidirectional"))
    )
    (net (code "8") (name "EPD_BUSY") (class "Default")
      (node (ref "J1") (pin "9") (pinfunction "9_9") (pintype "bidirectional"))
      (node (ref "U$1") (pin "P$AD12") (pinfunction "P0.17_P$AD12") (pintype "bidirectional"))
    )
    (net (code "9") (name "EPD_CS") (class "Default")
      (node (ref "J1") (pin "12") (pinfunction "12_12") (pintype "bidirectional"))
      (node (ref "U$1") (pin "P$K2") (pinfunction "P0.05/AIN3_P$K2") (pintype "bidirectional"))
    )
    (net (code "10") (name "EPD_DC") (class "Default")
      (node (ref "J1") (pin "11") (pinfunction "11_11") (pintype "bidirectional"))
      (node (ref "U$1") (pin "P$AD10") (pinfunction "P0.15_P$AD10") (pintype "bidirectional"))
    )
    (net (code "11") (name "EPD_RST") (class "Default")
      (node (ref "J1") (pin "10") (pinfunction "10_10") (pintype "bidirectional"))
      (node (ref "U$1") (pin "P$AC11") (pinfunction "P0.16_P$AC11") (pintype "bidirectional"))
    )
    (net (code "12") (name "GDR") (class "Default")
      (node (ref "J1") (pin "2") (pinfunction "2_2") (pintype "bidirectional"))
      (node (ref "Q3") (pin "1") (pinfunction "G_1") (pintype "bidirectional"))
      (node (ref "R2_EP_DR") (pin "2") (pinfunction "2_2") (pintype "bidirectional"))
    )
    (net (code "13") (name "GND") (class "Default")
      (node (ref "C1") (pin "1") (pinfunction "1_1") (pintype "passive"))
      (node (ref "C1-EP-DR") (pin "2") (pinfunction "2_2") (pintype "passive"))
      (node (ref "C10") (pin "1") (pinfunction "1_1") (pintype "passive"))
      (node (ref "C11") (pin "1") (pinfunction "1_1") (pintype "passive"))
      (node (ref "C12") (pin "1") (pinfunction "1_1") (pintype "passive"))
      (node (ref "C13") (pin "2") (pinfunction "2_2") (pintype "passive"))
      (node (ref "C14") (pin "2") (pinfunction "2_2") (pintype "passive"))
      (node (ref "C15") (pin "1") (pinfunction "1_1") (pintype "passive"))
      (node (ref "C16") (pin "1") (pinfunction "1_1") (pintype "passive"))
      (node (ref "C17") (pin "2") (pinfunction "2_2") (pintype "passive"))
      (node (ref "C18") (pin "2") (pinfunction "2_2") (pintype "passive"))
      (node (ref "C19") (pin "1") (pinfunction "1_1") (pintype "passive"))
      (node (ref "C2") (pin "1") (pinfunction "1_1") (pintype "passive"))
      (node (ref "C20") (pin "2") (pinfunction "2_2") (pintype "passive"))
      (node (ref "C21") (pin "2") (pinfunction "2_2") (pintype "passive"))
      (node (ref "C22") (pin "1") (pinfunction "1_1") (pintype "passive"))
      (node (ref "C23") (pin "2") (pinfunction "2_2") (pintype "passive"))
      (node (ref "C24") (pin "1") (pinfunction "1_1") (pintype "passive"))
      (node (ref "C25") (pin "1") (pinfunction "1_1") (pintype "passive"))
      (node (ref "C27") (pin "2") (pinfunction "2_2") (pintype "passive"))
      (node (ref "C29") (pin "1") (pinfunction "1_1") (pintype "passive"))
      (node (ref "C3") (pin "1") (pinfunction "1_1") (pintype "passive"))
      (node (ref "C30") (pin "1") (pinfunction "1_1") (pintype "passive"))
      (node (ref "C31") (pin "1") (pinfunction "1_1") (pintype "passive"))
      (node (ref "C32") (pin "1") (pinfunction "1_1") (pintype "passive"))
      (node (ref "C33") (pin "2") (pinfunction "2_2") (pintype "passive"))
      (node (ref "C34") (pin "1") (pinfunction "1_1") (pintype "passive"))
      (node (ref "C37") (pin "1") (pinfunction "1_1") (pintype "passive"))
      (node (ref "C38") (pin "1") (pinfunction "1_1") (pintype "passive"))
      (node (ref "C39") (pin "2") (pinfunction "2_2") (pintype "passive"))
      (node (ref "C4") (pin "1") (pinfunction "1_1") (pintype "passive"))
      (node (ref "C42") (pin "2") (pinfunction "2_2") (pintype "passive"))
      (node (ref "C43") (pin "2") (pinfunction "2_2") (pintype "passive"))
      (node (ref "C5") (pin "1") (pinfunction "1_1") (pintype "passive"))
      (node (ref "C6") (pin "2") (pinfunction "2_2") (pintype "passive"))
      (node (ref "C7") (pin "1") (pinfunction "1_1") (pintype "passive"))
      (node (ref "C8") (pin "1") (pinfunction "1_1") (pintype "passive"))
      (node (ref "C9") (pin "1") (pinfunction "1_1") (pintype "passive"))
      (node (ref "D2") (pin "1") (pinfunction "K_1") (pintype "bidirectional"))
      (node (ref "D3") (pin "2") (pinfunction "GND_2") (pintype "bidirectional"))
      (node (ref "EPD_C1") (pin "1") (pinfunction "1_1") (pintype "passive"))
      (node (ref "EPD_C10") (pin "1") (pinfunction "1_1") (pintype "passive"))
      (node (ref "EPD_C11") (pin "1") (pinfunction "1_1") (pintype "passive"))
      (node (ref "EPD_C12") (pin "1") (pinfunction "1_1") (pintype "passive"))
      (node (ref "EPD_C2") (pin "1") (pinfunction "1_1") (pintype "passive"))
      (node (ref "EPD_C5") (pin "1") (pinfunction "1_1") (pintype "passive"))
      (node (ref "EPD_C6") (pin "1") (pinfunction "1_1") (pintype "passive"))
      (node (ref "EPD_C7") (pin "1") (pinfunction "1_1") (pintype "passive"))
      (node (ref "EPD_C8") (pin "1") (pinfunction "1_1") (pintype "passive"))
      (node (ref "EPD_C9") (pin "1") (pinfunction "1_1") (pintype "passive"))
      (node (ref "IC1") (pin "D2") (pinfunction "GND_D2") (pintype "bidirectional"))
      (node (ref "IC2") (pin "B1") (pinfunction "IN/TRIG_B1") (pintype "bidirectional"))
      (node (ref "IC2") (pin "B3") (pinfunction "GND_B3") (pintype "bidirectional"))
      (node (ref "IC3") (pin "8") (pinfunction "GNDIO_8") (pintype "bidirectional"))
      (node (ref "IC3") (pin "9") (pinfunction "GND_9") (pintype "bidirectional"))
      (node (ref "IC9") (pin "B1") (pinfunction "VSEL_B1") (pintype "bidirectional"))
      (node (ref "IC9") (pin "C2") (pinfunction "PGND_1_C2") (pintype "bidirectional"))
      (node (ref "IC9") (pin "C3") (pinfunction "PGND_2_C3") (pintype "bidirectional"))
      (node (ref "J1") (pin "17") (pinfunction "17_17") (pintype "bidirectional"))
      (node (ref "J1") (pin "8") (pinfunction "8_8") (pintype "bidirectional"))
      (node (ref "J1") (pin "MP1") (pinfunction "MP1_MP1") (pintype "bidirectional"))
      (node (ref "J1") (pin "MP2") (pinfunction "MP2_MP2") (pintype "bidirectional"))
      (node (ref "J2") (pin "3") (pinfunction "3_3") (pintype "bidirectional"))
      (node (ref "J2") (pin "5") (pinfunction "5_5") (pintype "bidirectional"))
      (node (ref "J4") (pin "A12_B1") (pinfunction "GND_A12_B1") (pintype "power_in"))
      (node (ref "J4") (pin "A1_B12") (pinfunction "GND_A1_B12") (pintype "power_in"))
      (node (ref "J4") (pin "SH1") (pinfunction "SHIELD_SH1") (pintype "passive"))
      (node (ref "J4") (pin "SH2") (pinfunction "SHIELD_SH2") (pintype "passive"))
      (node (ref "J4") (pin "SH3") (pinfunction "SHIELD_SH3") (pintype "passive"))
      (node (ref "J4") (pin "SH4") (pinfunction "SHIELD_SH4") (pintype "passive"))
      (node (ref "R1_USB") (pin "1") (pinfunction "1_1") (pintype "bidirectional"))
      (node (ref "R2_EP_DR") (pin "1") (pinfunction "1_1") (pintype "bidirectional"))
      (node (ref "R2_USB") (pin "2") (pinfunction "2_2") (pintype "bidirectional"))
      (node (ref "R3") (pin "1") (pinfunction "1_1") (pintype "bidirectional"))
      (node (ref "R9") (pin "1") (pinfunction "1_1") (pintype "bidirectional"))
      (node (ref "R_TYPE_SEL") (pin "1") (pinfunction "1_1") (pintype "bidirectional"))
      (node (ref "SJ1") (pin "1") (pinfunction "1_1") (pintype "passive"))
      (node (ref "SW_DN") (pin "1") (pinfunction "1_1") (pintype "passive"))
      (node (ref "SW_ENT") (pin "1") (pinfunction "1_1") (pintype "passive"))
      (node (ref "SW_UP") (pin "1") (pinfunction "1_1") (pintype "passive"))
      (node (ref "TP_BAT_GND") (pin "TP") (pinfunction "TP_TP") (pintype "input"))
      (node (ref "TP_GND") (pin "TP") (pinfunction "TP_TP") (pintype "input"))
      (node (ref "U$1") (pin "P$74") (pinfunction "VSS_PAD_P$74") (pintype "bidirectional"))
      (node (ref "U$1") (pin "P$75") (pinfunction "VSS_PAD_P$75") (pintype "bidirectional"))
      (node (ref "U$1") (pin "P$76") (pinfunction "VSS_PAD_P$76") (pintype "bidirectional"))
      (node (ref "U$1") (pin "P$77") (pinfunction "VSS_PAD_P$77") (pintype "bidirectional"))
      (node (ref "U$1") (pin "P$78") (pinfunction "VSS_PAD_P$78") (pintype "bidirectional"))
      (node (ref "U$1") (pin "P$79") (pinfunction "VSS_PAD_P$79") (pintype "bidirectional"))
      (node (ref "U$1") (pin "P$80") (pinfunction "VSS_PAD_P$80") (pintype "bidirectional"))
      (node (ref "U$1") (pin "P$81") (pinfunction "VSS_PAD_P$81") (pintype "bidirectional"))
      (node (ref "U$1") (pin "P$82") (pinfunction "VSS_PAD_P$82") (pintype "bidirectional"))
      (node (ref "U$1") (pin "P$83") (pinfunction "VSS_PAD_P$83") (pintype "bidirectional"))
      (node (ref "U$1") (pin "P$84") (pinfunction "VSS_PAD_P$84") (pintype "bidirectional"))
      (node (ref "U$1") (pin "P$85") (pinfunction "VSS_PAD_P$85") (pintype "bidirectional"))
      (node (ref "U$1") (pin "P$86") (pinfunction "VSS_PAD_P$86") (pintype "bidirectional"))
      (node (ref "U$1") (pin "P$87") (pinfunction "VSS_PAD_P$87") (pintype "bidirectional"))
      (node (ref "U$1") (pin "P$88") (pinfunction "VSS_PAD_P$88") (pintype "bidirectional"))
      (node (ref "U$1") (pin "P$89") (pinfunction "VSS_PAD_P$89") (pintype "bidirectional"))
      (node (ref "U$1") (pin "P$90") (pinfunction "VSS_PAD_P$90") (pintype "bidirectional"))
      (node (ref "U$1") (pin "P$B7") (pinfunction "VSS_P$B7") (pintype "power_in"))
      (node (ref "U$1") (pin "P$F23") (pinfunction "VSS_PA_P$F23") (pintype "bidirectional"))
      (node (ref "U1") (pin "1") (pinfunction "CTG_1") (pintype "power_in"))
      (node (ref "U1") (pin "4") (pinfunction "GND_4") (pintype "power_in"))
      (node (ref "U1") (pin "6") (pinfunction "QSTRT_6") (pintype "input"))
      (node (ref "U1") (pin "9") (pinfunction "EP_9") (pintype "power_in"))
      (node (ref "X1") (pin "2") (pinfunction "2_2") (pintype "passive"))
      (node (ref "X1") (pin "4") (pinfunction "4_4") (pintype "passive"))
    )
    (net (code "14") (name "HAPTIC_EN") (class "Default")
      (node (ref "IC2") (pin "A1") (pinfunction "EN_A1") (pintype "bidirectional"))
      (node (ref "U$1") (pin "P$U1") (pinfunction "P0.12_P$U1") (pintype "bidirectional"))
    )
    (net (code "15") (name "IMU_INT1") (class "Default")
      (node (ref "IC3") (pin "5") (pinfunction "INT1_5") (pintype "bidirectional"))
      (node (ref "U$1") (pin "P$N1") (pinfunction "P0.08_P$N1") (pintype "bidirectional"))
    )
    (net (code "16") (name "IMU_INT2") (class "Default")
      (node (ref "IC3") (pin "6") (pinfunction "INT2_6") (pintype "bidirectional"))
      (node (ref "U$1") (pin "P$P2") (pinfunction "P1.08_P$P2") (pintype "bidirectional"))
    )
    (net (code "17") (name "LX1") (class "Default")
      (node (ref "IC9") (pin "B2") (pinfunction "SW1_1_B2") (pintype "bidirectional"))
      (node (ref "IC9") (pin "B3") (pinfunction "SW1_2_B3") (pintype "bidirectional"))
      (node (ref "L7") (pin "1") (pinfunction "1_1") (pintype "bidirectional"))
    )
    (net (code "18") (name "LX2") (class "Default")
      (node (ref "IC9") (pin "D2") (pinfunction "SW2_1_D2") (pintype "bidirectional"))
      (node (ref "IC9") (pin "D3") (pinfunction "SW2_2_D3") (pintype "bidirectional"))
      (node (ref "L7") (pin "2") (pinfunction "2_2") (pintype "bidirectional"))
    )
    (net (code "19") (name "MOSI") (class "Default")
      (node (ref "J1") (pin "14") (pinfunction "14_14") (pintype "bidirectional"))
      (node (ref "U$1") (pin "P$B13") (pinfunction "P0.03/AIN1_P$B13") (pintype "bidirectional"))
    )
    (net (code "20") (name "Net-(ANT1-FEED)") (class "Default")
      (node (ref "ANT1") (pin "1") (pinfunction "FEED_1") (pintype "input"))
      (node (ref "C22") (pin "2") (pinfunction "2_2") (pintype "passive"))
      (node (ref "C4") (pin "2") (pinfunction "2_2") (pintype "passive"))
      (node (ref "L1") (pin "2") (pinfunction "2_2") (pintype "passive"))
    )
    (net (code "21") (name "Net-(D2-A)") (class "Default")
      (node (ref "C2-EP-DR") (pin "1") (pinfunction "1_1") (pintype "passive"))
      (node (ref "D2") (pin "2") (pinfunction "A_2") (pintype "bidirectional"))
      (node (ref "D4") (pin "1") (pinfunction "K_1") (pintype "bidirectional"))
    )
    (net (code "22") (name "Net-(D5-A)") (class "Default")
      (node (ref "C2-EP-DR") (pin "2") (pinfunction "2_2") (pintype "passive"))
      (node (ref "D5") (pin "2") (pinfunction "A_2") (pintype "bidirectional"))
      (node (ref "L5") (pin "1") (pinfunction "1_1") (pintype "passive"))
      (node (ref "Q3") (pin "3") (pinfunction "D_3") (pintype "bidirectional"))
    )
    (net (code "23") (name "Net-(EPD_C1-Pad2)") (class "Default")
      (node (ref "EPD_C1") (pin "2") (pinfunction "2_2") (pintype "passive"))
      (node (ref "J1") (pin "5") (pinfunction "5_5") (pintype "bidirectional"))
    )
    (net (code "24") (name "Net-(EPD_C2-Pad2)") (class "Default")
      (node (ref "EPD_C2") (pin "2") (pinfunction "2_2") (pintype "passive"))
      (node (ref "J1") (pin "4") (pinfunction "4_4") (pintype "bidirectional"))
    )
    (net (code "25") (name "Net-(EPD_C6-Pad2)") (class "Default")
      (node (ref "EPD_C6") (pin "2") (pinfunction "2_2") (pintype "passive"))
      (node (ref "J1") (pin "18") (pinfunction "18_18") (pintype "bidirectional"))
    )
    (net (code "26") (name "Net-(EPD_C7-Pad2)") (class "Default")
      (node (ref "EPD_C7") (pin "2") (pinfunction "2_2") (pintype "passive"))
      (node (ref "J1") (pin "19") (pinfunction "19_19") (pintype "bidirectional"))
    )
    (net (code "27") (name "Net-(EPD_C8-Pad2)") (class "Default")
      (node (ref "EPD_C8") (pin "2") (pinfunction "2_2") (pintype "passive"))
      (node (ref "J1") (pin "20") (pinfunction "20_20") (pintype "bidirectional"))
    )
    (net (code "28") (name "Net-(EPD_C10-Pad2)") (class "Default")
      (node (ref "EPD_C10") (pin "2") (pinfunction "2_2") (pintype "passive"))
      (node (ref "J1") (pin "22") (pinfunction "22_22") (pintype "bidirectional"))
    )
    (net (code "29") (name "Net-(EPD_C12-Pad2)") (class "Default")
      (node (ref "EPD_C12") (pin "2") (pinfunction "2_2") (pintype "passive"))
      (node (ref "J1") (pin "24") (pinfunction "24_24") (pintype "bidirectional"))
    )
    (net (code "30") (name "Net-(IC1-TS{slash}MR)") (class "Default")
      (node (ref "IC1") (pin "D1") (pinfunction "TS/MR_D1") (pintype "bidirectional"))
      (node (ref "R9") (pin "2") (pinfunction "2_2") (pintype "bidirectional"))
    )
    (net (code "31") (name "Net-(IC2-REG)") (class "Default")
      (node (ref "C32") (pin "2") (pinfunction "2_2") (pintype "passive"))
      (node (ref "IC2") (pin "A2") (pinfunction "REG_A2") (pintype "bidirectional"))
    )
    (net (code "32") (name "Net-(IC3-SDO)") (class "Default")
      (node (ref "IC3") (pin "1") (pinfunction "SDO_1") (pintype "bidirectional"))
      (node (ref "R3") (pin "2") (pinfunction "2_2") (pintype "bidirectional"))
    )
    (net (code "33") (name "Net-(IC9-SCL)") (class "Default")
      (node (ref "IC9") (pin "D1") (pinfunction "SCL_D1") (pintype "bidirectional"))
      (node (ref "R1") (pin "2") (pinfunction "2_2") (pintype "bidirectional"))
    )
    (net (code "34") (name "Net-(IC9-SDA)") (class "Default")
      (node (ref "IC9") (pin "E1") (pinfunction "SDA_E1") (pintype "bidirectional"))
      (node (ref "R2") (pin "2") (pinfunction "2_2") (pintype "bidirectional"))
    )
    (net (code "35") (name "Net-(J4-CC1)") (class "Default")
      (node (ref "J4") (pin "A5") (pinfunction "CC1_A5") (pintype "bidirectional"))
      (node (ref "R1_USB") (pin "2") (pinfunction "2_2") (pintype "bidirectional"))
    )
    (net (code "36") (name "Net-(J4-CC2)") (class "Default")
      (node (ref "J4") (pin "B5") (pinfunction "CC2_B5") (pintype "bidirectional"))
      (node (ref "R2_USB") (pin "1") (pinfunction "1_1") (pintype "bidirectional"))
    )
    (net (code "37") (name "Net-(L2-Pad2)") (class "Default")
      (node (ref "L2") (pin "2") (pinfunction "2_2") (pintype "passive"))
      (node (ref "L3") (pin "2") (pinfunction "2_2") (pintype "passive"))
    )
    (net (code "38") (name "Net-(R1_EP_DR-Pad1)") (class "Default")
      (node (ref "R1_EP_DR") (pin "1") (pinfunction "1_1") (pintype "bidirectional"))
      (node (ref "R_TYPE_SEL") (pin "2") (pinfunction "2_2") (pintype "bidirectional"))
      (node (ref "SJ1") (pin "2") (pinfunction "2_2") (pintype "passive"))
    )
    (net (code "39") (name "Net-(U$1-ANT)") (class "Default")
      (node (ref "C3") (pin "2") (pinfunction "2_2") (pintype "passive"))
      (node (ref "L1") (pin "1") (pinfunction "1_1") (pintype "passive"))
      (node (ref "U$1") (pin "P$H23") (pinfunction "ANT_P$H23") (pintype "bidirectional"))
    )
    (net (code "40") (name "Net-(U$1-DCC)") (class "Default")
      (node (ref "L2") (pin "1") (pinfunction "1_1") (pintype "passive"))
      (node (ref "U$1") (pin "P$B3") (pinfunction "DCC_P$B3") (pintype "output"))
    )
    (net (code "41") (name "Net-(U$1-DEC1)") (class "Default")
      (node (ref "C5") (pin "2") (pinfunction "2_2") (pintype "passive"))
      (node (ref "U$1") (pin "P$C1") (pinfunction "DEC1_P$C1") (pintype "power_in"))
    )
    (net (code "42") (name "Net-(U$1-DEC2)") (class "Default")
      (node (ref "C13") (pin "1") (pinfunction "1_1") (pintype "passive"))
      (node (ref "U$1") (pin "P$A18") (pinfunction "DEC2_P$A18") (pintype "bidirectional"))
    )
    (net (code "43") (name "Net-(U$1-DEC3)") (class "Default")
      (node (ref "C11") (pin "2") (pinfunction "2_2") (pintype "passive"))
      (node (ref "U$1") (pin "P$D23") (pinfunction "DEC3_P$D23") (pintype "bidirectional"))
    )
    (net (code "44") (name "Net-(U$1-DEC3V3)") (class "Default")
      (node (ref "C20") (pin "1") (pinfunction "1_1") (pintype "passive"))
      (node (ref "U$1") (pin "P$AC5") (pinfunction "DEC3V3_P$AC5") (pintype "bidirectional"))
    )
    (net (code "45") (name "Net-(U$1-DEC4)") (class "Default")
      (node (ref "C10") (pin "2") (pinfunction "2_2") (pintype "passive"))
      (node (ref "C15") (pin "2") (pinfunction "2_2") (pintype "passive"))
      (node (ref "C16") (pin "2") (pinfunction "2_2") (pintype "passive"))
      (node (ref "L3") (pin "1") (pinfunction "1_1") (pintype "passive"))
      (node (ref "U$1") (pin "P$B5") (pinfunction "DEC4_P$B5") (pintype "power_in"))
      (node (ref "U$1") (pin "P$E24") (pinfunction "DEC6_P$E24") (pintype "bidirectional"))
    )
    (net (code "46") (name "Net-(U$1-DEC5)") (class "Default")
      (node (ref "C9") (pin "2") (pinfunction "2_2") (pintype "passive"))
      (node (ref "U$1") (pin "P$N24") (pinfunction "DEC5_P$N24") (pintype "bidirectional"))
    )
    (net (code "47") (name "Net-(U$1-P0.00{slash}XL1)") (class "Default")
      (node (ref "C17") (pin "1") (pinfunction "1_1") (pintype "passive"))
      (node (ref "U$1") (pin "P$D2") (pinfunction "P0.00/XL1_P$D2") (pintype "bidirectional"))
      (node (ref "X2") (pin "2") (pinfunction "2_2") (pintype "passive"))
    )
    (net (code "48") (name "Net-(U$1-P0.01{slash}XL2)") (class "Default")
      (node (ref "C18") (pin "1") (pinfunction "1_1") (pintype "passive"))
      (node (ref "U$1") (pin "P$F2") (pinfunction "P0.01/XL2_P$F2") (pintype "bidirectional"))
      (node (ref "X2") (pin "1") (pinfunction "1_1") (pintype "passive"))
    )
    (net (code "49") (name "Net-(U$1-XC1)") (class "Default")
      (node (ref "C1") (pin "2") (pinfunction "2_2") (pintype "passive"))
      (node (ref "U$1") (pin "P$B24") (pinfunction "XC1_P$B24") (pintype "input"))
      (node (ref "X1") (pin "1") (pinfunction "1_1") (pintype "passive"))
    )
    (net (code "50") (name "Net-(U$1-XC2)") (class "Default")
      (node (ref "C2") (pin "2") (pinfunction "2_2") (pintype "passive"))
      (node (ref "U$1") (pin "P$A23") (pinfunction "XC2_P$A23") (pintype "output"))
      (node (ref "X1") (pin "3") (pinfunction "3_3") (pintype "passive"))
    )
    (net (code "51") (name "OUT+") (class "Default")
      (node (ref "IC2") (pin "A3") (pinfunction "OUT+_A3") (pintype "bidirectional"))
      (node (ref "TP_OP") (pin "TP") (pinfunction "TP_TP") (pintype "input"))
    )
    (net (code "52") (name "OUT-") (class "Default")
      (node (ref "IC2") (pin "C3") (pinfunction "OUT-_C3") (pintype "bidirectional"))
      (node (ref "TP_ON") (pin "TP") (pinfunction "TP_TP") (pintype "input"))
    )
    (net (code "53") (name "P0.04") (class "Default")
      (node (ref "U$1") (pin "P$J1") (pinfunction "P0.04/AIN2_P$J1") (pintype "bidirectional"))
    )
    (net (code "54") (name "P0.09") (class "Default")
      (node (ref "U$1") (pin "P$L24") (pinfunction "P0.09/NFC1_P$L24") (pintype "bidirectional"))
    )
    (net (code "55") (name "P0.13") (class "Default")
      (node (ref "C30") (pin "2") (pinfunction "2_2") (pintype "passive"))
      (node (ref "R5") (pin "1") (pinfunction "1_1") (pintype "bidirectional"))
      (node (ref "SW_UP") (pin "2") (pinfunction "2_2") (pintype "passive"))
      (node (ref "U$1") (pin "P$AD8") (pinfunction "P0.13_P$AD8") (pintype "bidirectional"))
    )
    (net (code "56") (name "P0.14") (class "Default")
      (node (ref "C31") (pin "2") (pinfunction "2_2") (pintype "passive"))
      (node (ref "R8") (pin "1") (pinfunction "1_1") (pintype "bidirectional"))
      (node (ref "SW_ENT") (pin "2") (pinfunction "2_2") (pintype "passive"))
      (node (ref "U$1") (pin "P$AC9") (pinfunction "P0.14_P$AC9") (pintype "bidirectional"))
    )
    (net (code "57") (name "P0.19") (class "Default")
      (node (ref "U$1") (pin "P$AC15") (pinfunction "P0.19_P$AC15") (pintype "bidirectional"))
    )
    (net (code "58") (name "P0.20") (class "Default")
      (node (ref "U$1") (pin "P$AD16") (pinfunction "P0.20_P$AD16") (pintype "bidirectional"))
    )
    (net (code "59") (name "P0.21") (class "Default")
      (node (ref "U$1") (pin "P$AC17") (pinfunction "P0.21_P$AC17") (pintype "bidirectional"))
    )
    (net (code "60") (name "P0.22") (class "Default")
      (node (ref "U$1") (pin "P$AD18") (pinfunction "P0.22_P$AD18") (pintype "bidirectional"))
    )
    (net (code "61") (name "P0.23") (class "Default")
      (node (ref "U$1") (pin "P$AC19") (pinfunction "P0.23_P$AC19") (pintype "bidirectional"))
    )
    (net (code "62") (name "P0.24") (class "Default")
      (node (ref "U$1") (pin "P$AD20") (pinfunction "P0.24_P$AD20") (pintype "bidirectional"))
    )
    (net (code "63") (name "P0.25") (class "Default")
      (node (ref "U$1") (pin "P$AC21") (pinfunction "P0.25_P$AC21") (pintype "bidirectional"))
    )
    (net (code "64") (name "P0.26") (class "Default")
      (node (ref "U$1") (pin "P$G1") (pinfunction "P0.26_P$G1") (pintype "bidirectional"))
    )
    (net (code "65") (name "P0.27") (class "Default")
      (node (ref "U$1") (pin "P$H2") (pinfunction "P0.27_P$H2") (pintype "bidirectional"))
    )
    (net (code "66") (name "P0.28") (class "Default")
      (node (ref "U$1") (pin "P$B11") (pinfunction "P0.28/AIN4_P$B11") (pintype "bidirectional"))
    )
    (net (code "67") (name "P0.29") (class "Default")
      (node (ref "U$1") (pin "P$A10") (pinfunction "P0.29/AIN5_P$A10") (pintype "bidirectional"))
    )
    (net (code "68") (name "P0.30") (class "Default")
      (node (ref "U$1") (pin "P$B9") (pinfunction "P0.30/AIN6_P$B9") (pintype "bidirectional"))
    )
    (net (code "69") (name "P0.31") (class "Default")
      (node (ref "U$1") (pin "P$A8") (pinfunction "P0.31/AIN7_P$A8") (pintype "bidirectional"))
    )
    (net (code "70") (name "P1.01") (class "Default")
      (node (ref "Q1") (pin "1") (pinfunction "G_1") (pintype "bidirectional"))
      (node (ref "R1_PWR_EPD") (pin "1") (pinfunction "1_1") (pintype "bidirectional"))
      (node (ref "U$1") (pin "P$Y23") (pinfunction "P1.01_P$Y23") (pintype "bidirectional"))
    )
    (net (code "71") (name "P1.02") (class "Default")
      (node (ref "C29") (pin "2") (pinfunction "2_2") (pintype "passive"))
      (node (ref "R7") (pin "1") (pinfunction "1_1") (pintype "bidirectional"))
      (node (ref "SW_DN") (pin "2") (pinfunction "2_2") (pintype "passive"))
      (node (ref "U$1") (pin "P$W24") (pinfunction "P1.02_P$W24") (pintype "bidirectional"))
    )
    (net (code "72") (name "P1.03") (class "Default")
      (node (ref "U$1") (pin "P$V23") (pinfunction "P1.03_P$V23") (pintype "bidirectional"))
    )
    (net (code "73") (name "P1.04") (class "Default")
      (node (ref "U$1") (pin "P$U24") (pinfunction "P1.04_P$U24") (pintype "bidirectional"))
    )
    (net (code "74") (name "P1.05") (class "Default")
      (node (ref "U$1") (pin "P$T23") (pinfunction "P1.05_P$T23") (pintype "bidirectional"))
    )
    (net (code "75") (name "P1.06") (class "Default")
      (node (ref "U$1") (pin "P$R24") (pinfunction "P1.06_P$R24") (pintype "bidirectional"))
    )
    (net (code "76") (name "P1.07") (class "Default")
      (node (ref "U$1") (pin "P$P23") (pinfunction "P1.07_P$P23") (pintype "bidirectional"))
    )
    (net (code "77") (name "P1.09") (class "Default")
      (node (ref "U$1") (pin "P$R1") (pinfunction "P1.09_P$R1") (pintype "bidirectional"))
    )
    (net (code "78") (name "P1.10") (class "Default")
      (node (ref "U$1") (pin "P$A20") (pinfunction "P1.10_P$A20") (pintype "bidirectional"))
    )
    (net (code "79") (name "P1.11") (class "Default")
      (node (ref "U$1") (pin "P$B19") (pinfunction "P1.11_P$B19") (pintype "bidirectional"))
    )
    (net (code "80") (name "P1.12") (class "Default")
      (node (ref "U$1") (pin "P$B17") (pinfunction "P1.12_P$B17") (pintype "bidirectional"))
    )
    (net (code "81") (name "P1.13") (class "Default")
      (node (ref "U$1") (pin "P$A16") (pinfunction "P1.13_P$A16") (pintype "bidirectional"))
    )
    (net (code "82") (name "P1.14") (class "Default")
      (node (ref "U$1") (pin "P$B15") (pinfunction "P1.14_P$B15") (pintype "bidirectional"))
    )
    (net (code "83") (name "P1.15") (class "Default")
      (node (ref "U$1") (pin "P$A14") (pinfunction "P1.15_P$A14") (pintype "bidirectional"))
    )
    (net (code "84") (name "PMIC_INT") (class "Default")
      (node (ref "IC1") (pin "A1") (pinfunction "~{INT}_A1") (pintype "bidirectional"))
      (node (ref "U$1") (pin "P$T2") (pinfunction "P0.11_P$T2") (pintype "bidirectional"))
    )
    (net (code "85") (name "PREVGH") (class "Default")
      (node (ref "D5") (pin "1") (pinfunction "K_1") (pintype "bidirectional"))
      (node (ref "EPD_C9") (pin "2") (pinfunction "2_2") (pintype "passive"))
      (node (ref "J1") (pin "21") (pinfunction "21_21") (pintype "bidirectional"))
    )
    (net (code "86") (name "PREVGL") (class "Default")
      (node (ref "D4") (pin "2") (pinfunction "A_2") (pintype "bidirectional"))
      (node (ref "EPD_C11") (pin "2") (pinfunction "2_2") (pintype "passive"))
      (node (ref "J1") (pin "23") (pinfunction "23_23") (pintype "bidirectional"))
    )
    (net (code "87") (name "RESE") (class "Default")
      (node (ref "J1") (pin "3") (pinfunction "3_3") (pintype "bidirectional"))
      (node (ref "Q3") (pin "2") (pinfunction "S_2") (pintype "bidirectional"))
      (node (ref "R1_EP_DR") (pin "2") (pinfunction "2_2") (pintype "bidirectional"))
    )
    (net (code "88") (name "RESET") (class "Default")
      (node (ref "J2") (pin "6") (pinfunction "6_6") (pintype "bidirectional"))
      (node (ref "TP_RESET") (pin "TP") (pinfunction "TP_TP") (pintype "input"))
      (node (ref "U$1") (pin "P$AC13") (pinfunction "P0.18/RESET_P$AC13") (pintype "bidirectional"))
    )
    (net (code "89") (name "SCK") (class "Default")
      (node (ref "J1") (pin "13") (pinfunction "13_13") (pintype "bidirectional"))
      (node (ref "U$1") (pin "P$A12") (pinfunction "P0.02/AIN0_P$A12") (pintype "bidirectional"))
    )
    (net (code "90") (name "SCL") (class "Default")
      (node (ref "IC1") (pin "B1") (pinfunction "SCL_B1") (pintype "bidirectional"))
      (node (ref "IC2") (pin "C1") (pinfunction "SCL_C1") (pintype "bidirectional"))
      (node (ref "IC3") (pin "12") (pinfunction "SCX_12") (pintype "bidirectional"))
      (node (ref "R1") (pin "1") (pinfunction "1_1") (pintype "bidirectional"))
      (node (ref "R17") (pin "2") (pinfunction "2_2") (pintype "bidirectional"))
      (node (ref "TP_SCL") (pin "TP") (pinfunction "TP_TP") (pintype "input"))
      (node (ref "U$1") (pin "P$M2") (pinfunction "P0.07_P$M2") (pintype "bidirectional"))
      (node (ref "U1") (pin "7") (pinfunction "SCL_7") (pintype "input"))
    )
    (net (code "91") (name "SDA") (class "Default")
      (node (ref "IC1") (pin "C1") (pinfunction "SDA_C1") (pintype "bidirectional"))
      (node (ref "IC2") (pin "B2") (pinfunction "SDA_B2") (pintype "bidirectional"))
      (node (ref "IC3") (pin "2") (pinfunction "SDX_2") (pintype "bidirectional"))
      (node (ref "R18") (pin "2") (pinfunction "2_2") (pintype "bidirectional"))
      (node (ref "R2") (pin "1") (pinfunction "1_1") (pintype "bidirectional"))
      (node (ref "TP_SDA") (pin "TP") (pinfunction "TP_TP") (pintype "input"))
      (node (ref "U$1") (pin "P$L1") (pinfunction "P0.06_P$L1") (pintype "bidirectional"))
      (node (ref "U1") (pin "8") (pinfunction "SDA_8") (pintype "bidirectional"))
    )
    (net (code "92") (name "SWDCLK") (class "Default")
      (node (ref "J2") (pin "4") (pinfunction "4_4") (pintype "bidirectional"))
      (node (ref "TP_SWDCLK") (pin "TP") (pinfunction "TP_TP") (pintype "input"))
      (node (ref "U$1") (pin "P$AA24") (pinfunction "SWDCLK_P$AA24") (pintype "input"))
    )
    (net (code "93") (name "SWDIO") (class "Default")
      (node (ref "J2") (pin "2") (pinfunction "2_2") (pintype "bidirectional"))
      (node (ref "TP_SWDIO") (pin "TP") (pinfunction "TP_TP") (pintype "input"))
      (node (ref "U$1") (pin "P$AC24") (pinfunction "SWDIO_P$AC24") (pintype "bidirectional"))
    )
    (net (code "94") (name "SWO") (class "Default")
      (node (ref "TP_SWO") (pin "TP") (pinfunction "TP_TP") (pintype "input"))
      (node (ref "U$1") (pin "P$AD22") (pinfunction "P1.00_P$AD22") (pintype "bidirectional"))
    )
    (net (code "95") (name "VBAT") (class "Default")
      (node (ref "C27") (pin "1") (pinfunction "1_1") (pintype "passive"))
      (node (ref "C37") (pin "2") (pinfunction "2_2") (pintype "passive"))
      (node (ref "IC1") (pin "C2") (pinfunction "BAT_C2") (pintype "bidirectional"))
      (node (ref "TP_VBAT") (pin "TP") (pinfunction "TP_TP") (pintype "input"))
      (node (ref "U1") (pin "2") (pinfunction "CELL_2") (pintype "power_in"))
      (node (ref "U1") (pin "3") (pinfunction "VDD_3") (pintype "power_in"))
    )
    (net (code "96") (name "VBUS") (class "Default")
      (node (ref "C21") (pin "1") (pinfunction "1_1") (pintype "passive"))
      (node (ref "C38") (pin "2") (pinfunction "2_2") (pintype "passive"))
      (node (ref "C42") (pin "1") (pinfunction "1_1") (pintype "passive"))
      (node (ref "C43") (pin "1") (pinfunction "1_1") (pintype "passive"))
      (node (ref "D3") (pin "5") (pinfunction "VBUS_5") (pintype "bidirectional"))
      (node (ref "IC1") (pin "A2") (pinfunction "IN_A2") (pintype "bidirectional"))
      (node (ref "J4") (pin "A4_B9") (pinfunction "VBUS_A4_B9") (pintype "power_in"))
      (node (ref "J4") (pin "A9_B4") (pinfunction "VBUS_A9_B4") (pintype "power_in"))
      (node (ref "U$1") (pin "P$AD2") (pinfunction "VBUS_P$AD2") (pintype "power_in"))
    )
    (net (code "97") (name "VREG") (class "Default")
      (node (ref "C23") (pin "1") (pinfunction "1_1") (pintype "passive"))
      (node (ref "C24") (pin "2") (pinfunction "2_2") (pintype "passive"))
      (node (ref "C39") (pin "1") (pinfunction "1_1") (pintype "passive"))
      (node (ref "IC1") (pin "B2") (pinfunction "SYS_B2") (pintype "bidirectional"))
      (node (ref "IC9") (pin "A1") (pinfunction "EN_A1") (pintype "bidirectional"))
      (node (ref "IC9") (pin "A2") (pinfunction "VIN_1_A2") (pintype "bidirectional"))
      (node (ref "IC9") (pin "A3") (pinfunction "VIN_2_A3") (pintype "bidirectional"))
      (node (ref "TP_VREG") (pin "TP") (pinfunction "TP_TP") (pintype "input"))
    )
    (net (code "98") (name "unconnected-(ANT1-NC-Pad2)") (class "Default")
      (node (ref "ANT1") (pin "2") (pinfunction "NC_2") (pintype "no_connect"))
    )
    (net (code "99") (name "unconnected-(IC3-ASCL-Pad11)") (class "Default")
      (node (ref "IC3") (pin "11") (pinfunction "ASCL_11") (pintype "bidirectional"))
    )
    (net (code "100") (name "unconnected-(IC3-ASDA-Pad4)") (class "Default")
      (node (ref "IC3") (pin "4") (pinfunction "ASDA_4") (pintype "bidirectional"))
    )
    (net (code "101") (name "unconnected-(IC9-AGND-PadC1)") (class "Default")
      (node (ref "IC9") (pin "C1") (pinfunction "AGND_C1") (pintype "bidirectional"))
    )
    (net (code "102") (name "unconnected-(J1-Pad1)") (class "Default")
      (node (ref "J1") (pin "1") (pinfunction "1_1") (pintype "bidirectional"))
    )
    (net (code "103") (name "unconnected-(J1-Pad6)") (class "Default")
      (node (ref "J1") (pin "6") (pinfunction "6_6") (pintype "bidirectional"))
    )
    (net (code "104") (name "unconnected-(J1-Pad7)") (class "Default")
      (node (ref "J1") (pin "7") (pinfunction "7_7") (pintype "bidirectional"))
    )
    (net (code "105") (name "unconnected-(J4-SBU1-PadA8)") (class "Default")
      (node (ref "J4") (pin "A8") (pinfunction "SBU1_A8") (pintype "bidirectional"))
    )
    (net (code "106") (name "unconnected-(J4-SBU2-PadB8)") (class "Default")
      (node (ref "J4") (pin "B8") (pinfunction "SBU2_B8") (pintype "bidirectional"))
    )
    (net (code "107") (name "unconnected-(U$1-DCCH-PadP$AB2)") (class "Default")
      (node (ref "U$1") (pin "P$AB2") (pinfunction "DCCH_P$AB2") (pintype "bidirectional"))
    )
  )
)
